# Output.net
KiCad netlist of a schematic drawn in EAGLE
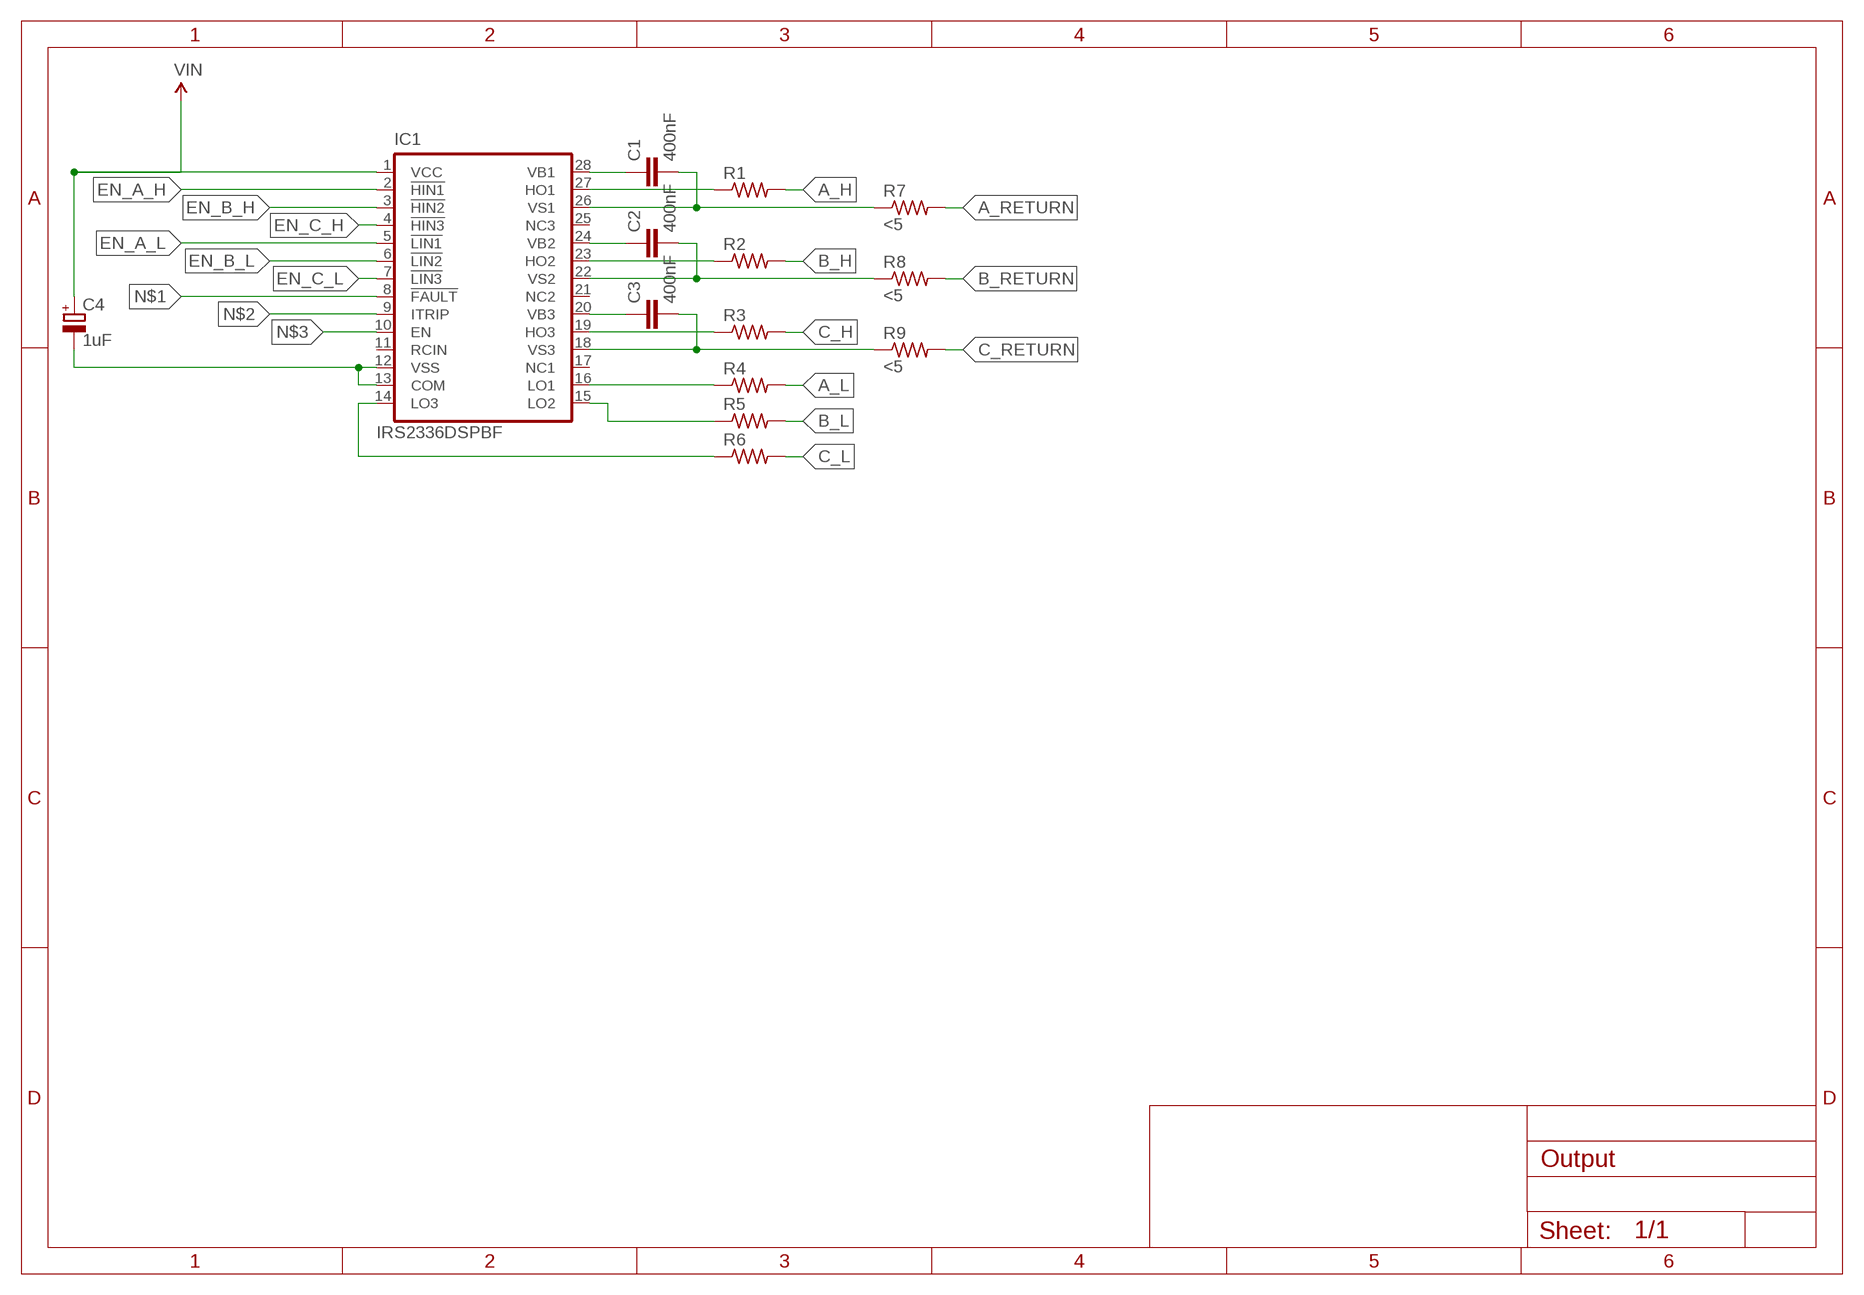
[diagram p0: schematic, sheet 1]

(export (version "E")
  (design (tool "Eeschema 10.0.6"))
  (components
    (comp (ref "C1")
      (value "400nF")
      (footprint "eagle-import:C050-050X075")
      (libsource (lib "eagle-import") (part "C-EU050-050X075"))
    )
    (comp (ref "C2")
      (value "400nF")
      (footprint "eagle-import:C050-050X075")
      (libsource (lib "eagle-import") (part "C-EU050-050X075"))
    )
    (comp (ref "C3")
      (value "400nF")
      (footprint "eagle-import:C050-050X075")
      (libsource (lib "eagle-import") (part "C-EU050-050X075"))
    )
    (comp (ref "C4")
      (value "1uF")
      (footprint "eagle-import:E2-5")
      (libsource (lib "eagle-import") (part "CPOL-EUE2-5"))
    )
    (comp (ref "IC1")
      (value "IRS2336DSPBF")
      (footprint "eagle-import:SOICW28")
      (libsource (lib "eagle-import") (part "IRS2336DSPBF"))
    )
    (comp (ref "R1")
      (value "R-US_0207/7")
      (footprint "eagle-import:0207_7")
      (libsource (lib "eagle-import") (part "R-US_0207/7"))
    )
    (comp (ref "R2")
      (value "R-US_0207/7")
      (footprint "eagle-import:0207_7")
      (libsource (lib "eagle-import") (part "R-US_0207/7"))
    )
    (comp (ref "R3")
      (value "R-US_0207/7")
      (footprint "eagle-import:0207_7")
      (libsource (lib "eagle-import") (part "R-US_0207/7"))
    )
    (comp (ref "R4")
      (value "R-US_0207/7")
      (footprint "eagle-import:0207_7")
      (libsource (lib "eagle-import") (part "R-US_0207/7"))
    )
    (comp (ref "R5")
      (value "R-US_0207/7")
      (footprint "eagle-import:0207_7")
      (libsource (lib "eagle-import") (part "R-US_0207/7"))
    )
    (comp (ref "R6")
      (value "R-US_0207/7")
      (footprint "eagle-import:0207_7")
      (libsource (lib "eagle-import") (part "R-US_0207/7"))
    )
    (comp (ref "R7")
      (value "<5")
      (footprint "eagle-import:0207_7")
      (libsource (lib "eagle-import") (part "R-US_0207/7"))
    )
    (comp (ref "R8")
      (value "<5")
      (footprint "eagle-import:0207_7")
      (libsource (lib "eagle-import") (part "R-US_0207/7"))
    )
    (comp (ref "R9")
      (value "<5")
      (footprint "eagle-import:0207_7")
      (libsource (lib "eagle-import") (part "R-US_0207/7"))
    )
  )
  (nets
    (net (code "1") (name "A_H") (class "Default")
      (node (ref "R1") (pin "2") (pinfunction "2_2") (pintype "passive"))
    )
    (net (code "2") (name "A_L") (class "Default")
      (node (ref "R4") (pin "2") (pinfunction "2_2") (pintype "passive"))
    )
    (net (code "3") (name "A_RETURN") (class "Default")
      (node (ref "R7") (pin "2") (pinfunction "2_2") (pintype "passive"))
    )
    (net (code "4") (name "B_H") (class "Default")
      (node (ref "R2") (pin "2") (pinfunction "2_2") (pintype "passive"))
    )
    (net (code "5") (name "B_L") (class "Default")
      (node (ref "R5") (pin "2") (pinfunction "2_2") (pintype "passive"))
    )
    (net (code "6") (name "B_RETURN") (class "Default")
      (node (ref "R8") (pin "2") (pinfunction "2_2") (pintype "passive"))
    )
    (net (code "7") (name "C_H") (class "Default")
      (node (ref "R3") (pin "2") (pinfunction "2_2") (pintype "passive"))
    )
    (net (code "8") (name "C_L") (class "Default")
      (node (ref "R6") (pin "2") (pinfunction "2_2") (pintype "passive"))
    )
    (net (code "9") (name "C_RETURN") (class "Default")
      (node (ref "R9") (pin "2") (pinfunction "2_2") (pintype "passive"))
    )
    (net (code "10") (name "EN_A_H") (class "Default")
      (node (ref "IC1") (pin "2") (pinfunction "~{HIN1}_2") (pintype "bidirectional"))
    )
    (net (code "11") (name "EN_A_L") (class "Default")
      (node (ref "IC1") (pin "5") (pinfunction "~{LIN1}_5") (pintype "input"))
    )
    (net (code "12") (name "EN_B_H") (class "Default")
      (node (ref "IC1") (pin "3") (pinfunction "~{HIN2}_3") (pintype "bidirectional"))
    )
    (net (code "13") (name "EN_B_L") (class "Default")
      (node (ref "IC1") (pin "6") (pinfunction "~{LIN2}_6") (pintype "input"))
    )
    (net (code "14") (name "EN_C_H") (class "Default")
      (node (ref "IC1") (pin "4") (pinfunction "~{HIN3}_4") (pintype "input"))
    )
    (net (code "15") (name "EN_C_L") (class "Default")
      (node (ref "IC1") (pin "7") (pinfunction "~{LIN3}_7") (pintype "input"))
    )
    (net (code "16") (name "N$1") (class "Default")
      (node (ref "IC1") (pin "8") (pinfunction "~{FAULT}_8") (pintype "input"))
    )
    (net (code "17") (name "N$2") (class "Default")
      (node (ref "IC1") (pin "9") (pinfunction "ITRIP_9") (pintype "input"))
    )
    (net (code "18") (name "N$3") (class "Default")
      (node (ref "IC1") (pin "10") (pinfunction "EN_10") (pintype "input"))
    )
    (net (code "19") (name "Net-(IC1-COM)") (class "Default")
      (node (ref "C4") (pin "-") (pinfunction "-_-") (pintype "passive"))
      (node (ref "IC1") (pin "12") (pinfunction "VSS_12") (pintype "output"))
      (node (ref "IC1") (pin "13") (pinfunction "COM_13") (pintype "input"))
    )
    (net (code "20") (name "Net-(IC1-HO1)") (class "Default")
      (node (ref "IC1") (pin "27") (pinfunction "HO1_27") (pintype "output"))
      (node (ref "R1") (pin "1") (pinfunction "1_1") (pintype "passive"))
    )
    (net (code "21") (name "Net-(IC1-HO2)") (class "Default")
      (node (ref "IC1") (pin "23") (pinfunction "HO2_23") (pintype "input"))
      (node (ref "R2") (pin "1") (pinfunction "1_1") (pintype "passive"))
    )
    (net (code "22") (name "Net-(IC1-HO3)") (class "Default")
      (node (ref "IC1") (pin "19") (pinfunction "HO3_19") (pintype "input"))
      (node (ref "R3") (pin "1") (pinfunction "1_1") (pintype "passive"))
    )
    (net (code "23") (name "Net-(IC1-LO1)") (class "Default")
      (node (ref "IC1") (pin "16") (pinfunction "LO1_16") (pintype "input"))
      (node (ref "R4") (pin "1") (pinfunction "1_1") (pintype "passive"))
    )
    (net (code "24") (name "Net-(IC1-LO2)") (class "Default")
      (node (ref "IC1") (pin "15") (pinfunction "LO2_15") (pintype "output"))
      (node (ref "R5") (pin "1") (pinfunction "1_1") (pintype "passive"))
    )
    (net (code "25") (name "Net-(IC1-LO3)") (class "Default")
      (node (ref "IC1") (pin "14") (pinfunction "LO3_14") (pintype "output"))
      (node (ref "R6") (pin "1") (pinfunction "1_1") (pintype "passive"))
    )
    (net (code "26") (name "Net-(IC1-VB1)") (class "Default")
      (node (ref "C1") (pin "1") (pinfunction "1_1") (pintype "passive"))
      (node (ref "IC1") (pin "28") (pinfunction "VB1_28") (pintype "input"))
    )
    (net (code "27") (name "Net-(IC1-VB2)") (class "Default")
      (node (ref "C2") (pin "1") (pinfunction "1_1") (pintype "passive"))
      (node (ref "IC1") (pin "24") (pinfunction "VB2_24") (pintype "input"))
    )
    (net (code "28") (name "Net-(IC1-VB3)") (class "Default")
      (node (ref "C3") (pin "1") (pinfunction "1_1") (pintype "passive"))
      (node (ref "IC1") (pin "20") (pinfunction "VB3_20") (pintype "input"))
    )
    (net (code "29") (name "Net-(IC1-VS1)") (class "Default")
      (node (ref "C1") (pin "2") (pinfunction "2_2") (pintype "passive"))
      (node (ref "IC1") (pin "26") (pinfunction "VS1_26") (pintype "output"))
      (node (ref "R7") (pin "1") (pinfunction "1_1") (pintype "passive"))
    )
    (net (code "30") (name "Net-(IC1-VS2)") (class "Default")
      (node (ref "C2") (pin "2") (pinfunction "2_2") (pintype "passive"))
      (node (ref "IC1") (pin "22") (pinfunction "VS2_22") (pintype "input"))
      (node (ref "R8") (pin "1") (pinfunction "1_1") (pintype "passive"))
    )
    (net (code "31") (name "Net-(IC1-VS3)") (class "Default")
      (node (ref "C3") (pin "2") (pinfunction "2_2") (pintype "passive"))
      (node (ref "IC1") (pin "18") (pinfunction "VS3_18") (pintype "output"))
      (node (ref "R9") (pin "1") (pinfunction "1_1") (pintype "passive"))
    )
    (net (code "32") (name "VIN") (class "Default")
      (node (ref "C4") (pin "+") (pinfunction "+_+") (pintype "passive"))
      (node (ref "IC1") (pin "1") (pinfunction "VCC_1") (pintype "bidirectional"))
    )
    (net (code "33") (name "unconnected-(IC1-NC1-Pad17)") (class "Default")
      (node (ref "IC1") (pin "17") (pinfunction "NC1_17") (pintype "output"))
    )
    (net (code "34") (name "unconnected-(IC1-NC2-Pad21)") (class "Default")
      (node (ref "IC1") (pin "21") (pinfunction "NC2_21") (pintype "input"))
    )
    (net (code "35") (name "unconnected-(IC1-NC3-Pad25)") (class "Default")
      (node (ref "IC1") (pin "25") (pinfunction "NC3_25") (pintype "input"))
    )
    (net (code "36") (name "unconnected-(IC1-RCIN-Pad11)") (class "Default")
      (node (ref "IC1") (pin "11") (pinfunction "RCIN_11") (pintype "output"))
    )
  )
)
